# AP_2_4G_5_0G.net
KiCad netlist of a schematic drawn in Altium Designer
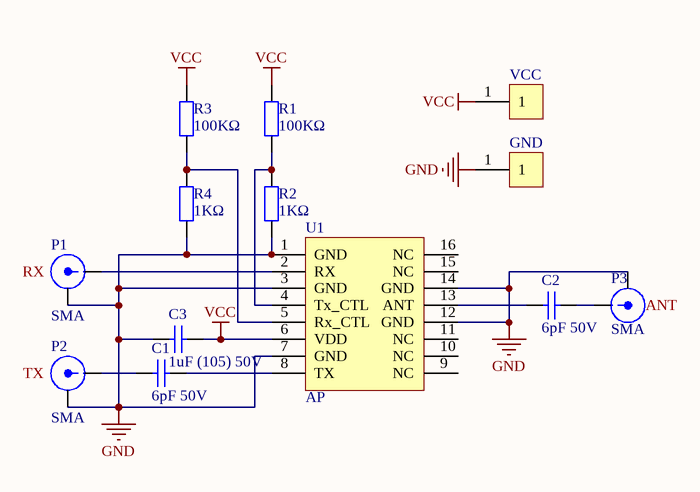
[diagram p0: AP_2.4G_5.0G.SchDoc]

(export (version "E")
  (design (tool "Eeschema 10.0.6"))
  (components
    (comp (ref "C1")
      (value "6pF 50V")
      (footprint "0805_C")
      (description "贴片电容")
      (libsource (lib "Cap") (part "0805 6pF (6R0) 0.25pF 50V"))
    )
    (comp (ref "C2")
      (value "6pF 50V")
      (footprint "0805_C")
      (description "贴片电容")
      (libsource (lib "Cap") (part "0805 6pF (6R0) 0.25pF 50V"))
    )
    (comp (ref "C3")
      (value "1uF (105) 50V")
      (footprint "0805_C")
      (description "贴片电容")
      (libsource (lib "Cap") (part "0805 1uF (105) 10% 50V"))
    )
    (comp (ref "GND")
      (value "SMDHDRX1")
      (footprint "SMDHDRX1")
      (description "SMA and Hole")
      (libsource (lib "Schlib_Cbp") (part "SMDHDRX1"))
    )
    (comp (ref "P1") (value "SMA") (footprint "SMA-KE") (libsource (lib "Schlib_Cbp") (part "SMA")))
    (comp (ref "P2") (value "SMA") (footprint "SMA-KE") (libsource (lib "Schlib_Cbp") (part "SMA")))
    (comp (ref "P3") (value "SMA") (footprint "SMA-KE") (libsource (lib "Schlib_Cbp") (part "SMA")))
    (comp (ref "R1")
      (value "100KΩ")
      (footprint "0805_R")
      (description "贴片电阻")
      (libsource (lib "RES") (part "0805 1KΩ (1001) 1%"))
    )
    (comp (ref "R2")
      (value "1KΩ")
      (footprint "0805_R")
      (description "贴片电阻")
      (libsource (lib "RES") (part "0805 1KΩ (1001) 1%"))
    )
    (comp (ref "R3")
      (value "100KΩ")
      (footprint "0805_R")
      (description "贴片电阻")
      (libsource (lib "RES") (part "0805 1KΩ (1001) 1%"))
    )
    (comp (ref "R4")
      (value "1KΩ")
      (footprint "0805_R")
      (description "贴片电阻")
      (libsource (lib "RES") (part "0805 1KΩ (1001) 1%"))
    )
    (comp (ref "U1")
      (value "AP")
      (footprint "QFN-16_3x3x05P")
      (description "AP_2.4G_5.0G")
      (libsource (lib "Schlib_Cbp") (part "LS5601"))
    )
    (comp (ref "VCC")
      (value "SMDHDRX1")
      (footprint "SMDHDRX1")
      (description "SMA and Hole")
      (libsource (lib "Schlib_Cbp") (part "SMDHDRX1"))
    )
  )
  (nets
    (net (code "1") (name "GND") (class "Default")
      (node (ref "C3") (pin "2") (pinfunction "2_2") (pintype "passive"))
      (node (ref "GND") (pin "1") (pinfunction "1_1") (pintype "passive"))
      (node (ref "P1") (pin "2") (pinfunction "Y_2") (pintype "passive"))
      (node (ref "P2") (pin "2") (pinfunction "Y_2") (pintype "passive"))
      (node (ref "P3") (pin "2") (pinfunction "Y_2") (pintype "passive"))
      (node (ref "R2") (pin "1") (pinfunction "1_1") (pintype "passive"))
      (node (ref "R4") (pin "1") (pinfunction "1_1") (pintype "passive"))
      (node (ref "U1") (pin "1") (pinfunction "GND_1") (pintype "passive"))
      (node (ref "U1") (pin "12") (pinfunction "GND_12") (pintype "passive"))
      (node (ref "U1") (pin "14") (pinfunction "GND_14") (pintype "passive"))
      (node (ref "U1") (pin "3") (pinfunction "GND_3") (pintype "passive"))
      (node (ref "U1") (pin "7") (pinfunction "GND_7") (pintype "passive"))
    )
    (net (code "2") (name "Net-(P1-X)") (class "Default")
      (node (ref "P1") (pin "1") (pinfunction "X_1") (pintype "passive"))
      (node (ref "U1") (pin "2") (pinfunction "RX_2") (pintype "passive"))
    )
    (net (code "3") (name "Net-(P2-X)") (class "Default")
      (node (ref "C1") (pin "1") (pinfunction "1_1") (pintype "passive"))
      (node (ref "P2") (pin "1") (pinfunction "X_1") (pintype "passive"))
    )
    (net (code "4") (name "Net-(P3-X)") (class "Default")
      (node (ref "C2") (pin "2") (pinfunction "2_2") (pintype "passive"))
      (node (ref "P3") (pin "1") (pinfunction "X_1") (pintype "passive"))
    )
    (net (code "5") (name "Net-(U1-ANT)") (class "Default")
      (node (ref "C2") (pin "1") (pinfunction "1_1") (pintype "passive"))
      (node (ref "U1") (pin "13") (pinfunction "ANT_13") (pintype "passive"))
    )
    (net (code "6") (name "Net-(U1-Rx_CTL)") (class "Default")
      (node (ref "R3") (pin "1") (pinfunction "1_1") (pintype "passive"))
      (node (ref "R4") (pin "2") (pinfunction "2_2") (pintype "passive"))
      (node (ref "U1") (pin "5") (pinfunction "Rx_CTL_5") (pintype "passive"))
    )
    (net (code "7") (name "Net-(U1-TX)") (class "Default")
      (node (ref "C1") (pin "2") (pinfunction "2_2") (pintype "passive"))
      (node (ref "U1") (pin "8") (pinfunction "TX_8") (pintype "passive"))
    )
    (net (code "8") (name "Net-(U1-Tx_CTL)") (class "Default")
      (node (ref "R1") (pin "1") (pinfunction "1_1") (pintype "passive"))
      (node (ref "R2") (pin "2") (pinfunction "2_2") (pintype "passive"))
      (node (ref "U1") (pin "4") (pinfunction "Tx_CTL_4") (pintype "passive"))
    )
    (net (code "9") (name "VCC") (class "Default")
      (node (ref "C3") (pin "1") (pinfunction "1_1") (pintype "passive"))
      (node (ref "R1") (pin "2") (pinfunction "2_2") (pintype "passive"))
      (node (ref "R3") (pin "2") (pinfunction "2_2") (pintype "passive"))
      (node (ref "U1") (pin "6") (pinfunction "VDD_6") (pintype "passive"))
      (node (ref "VCC") (pin "1") (pinfunction "1_1") (pintype "passive"))
    )
    (net (code "10") (name "unconnected-(U1-NC-Pad9)") (class "Default")
      (node (ref "U1") (pin "9") (pinfunction "NC_9") (pintype "passive"))
    )
    (net (code "11") (name "unconnected-(U1-NC-Pad10)") (class "Default")
      (node (ref "U1") (pin "10") (pinfunction "NC_10") (pintype "passive"))
    )
    (net (code "12") (name "unconnected-(U1-NC-Pad11)") (class "Default")
      (node (ref "U1") (pin "11") (pinfunction "NC_11") (pintype "passive"))
    )
    (net (code "13") (name "unconnected-(U1-NC-Pad15)") (class "Default")
      (node (ref "U1") (pin "15") (pinfunction "NC_15") (pintype "passive"))
    )
    (net (code "14") (name "unconnected-(U1-NC-Pad16)") (class "Default")
      (node (ref "U1") (pin "16") (pinfunction "NC_16") (pintype "passive"))
    )
  )
)
